# Half-Bridge.net
KiCad netlist of a schematic drawn in Altium Designer
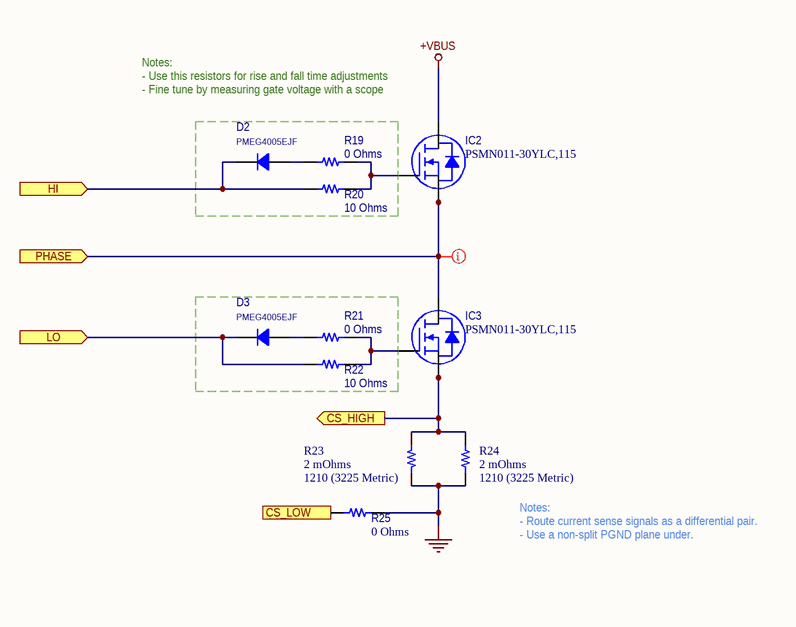
[diagram p0: Half-Bridge.SchDoc]

(export (version "E")
  (design (tool "Eeschema 10.0.6"))
  (components
    (comp (ref "D2")
      (value "PMEG4005EJF")
      (footprint "SOD323F")
      (description "PMEG4005EJ/SOD323/SOD2")
      (fields (field (name "MANUFACTURER") "Nexperia USA Inc."))
      (libsource (lib "Celestial Altium Library - altium_library") (part "Diode"))
    )
    (comp (ref "D3")
      (value "PMEG4005EJF")
      (footprint "SOD323F")
      (description "PMEG4005EJ/SOD323/SOD2")
      (fields (field (name "MANUFACTURER") "Nexperia USA Inc."))
      (libsource (lib "Celestial Altium Library - altium_library") (part "Diode"))
    )
    (comp (ref "IC2")
      (value "PSMN011-30YLC,115")
      (footprint "NXP LFPAK56 SOT669")
      (description "MOSFET N-CH 30V 37A LFPAK")
      (fields (field (name "MANUFACTURER") "Nexperia USA Inc."))
      (libsource (lib "Celestial Altium Library - altium_library") (part "NEXPERIA PSMN LFPAK MOSFET N-CH"))
    )
    (comp (ref "IC3")
      (value "PSMN011-30YLC,115")
      (footprint "NXP LFPAK56 SOT669")
      (description "MOSFET N-CH 30V 37A LFPAK")
      (fields (field (name "MANUFACTURER") "Nexperia USA Inc."))
      (libsource (lib "Celestial Altium Library - altium_library") (part "NEXPERIA PSMN LFPAK MOSFET N-CH"))
    )
    (comp (ref "R19")
      (value "0 Ohms")
      (footprint "RES 0402_1005")
      (description "RESA-AS 0402 0R JUMPER 63MW")
      (fields (field (name "PART NUMBER") "CR0402AJ/-000GAS") (field (name "MANUFACTURER") "Bourns Inc."))
      (libsource (lib "Celestial Altium Library - altium_library") (part "Resistor"))
    )
    (comp (ref "R20")
      (value "10 Ohms")
      (footprint "RES 0402_1005")
      (description "RES SMD 10 OHM 0.5% 1/16W 0402")
      (fields (field (name "PART NUMBER") "RR0510R-100-D") (field (name "MANUFACTURER") "Susumu"))
      (libsource (lib "Celestial Altium Library - altium_library") (part "Resistor"))
    )
    (comp (ref "R21")
      (value "0 Ohms")
      (footprint "RES 0402_1005")
      (description "RESA-AS 0402 0R JUMPER 63MW")
      (fields (field (name "PART NUMBER") "CR0402AJ/-000GAS") (field (name "MANUFACTURER") "Bourns Inc."))
      (libsource (lib "Celestial Altium Library - altium_library") (part "Resistor"))
    )
    (comp (ref "R22")
      (value "10 Ohms")
      (footprint "RES 0402_1005")
      (description "RES SMD 10 OHM 0.5% 1/16W 0402")
      (fields (field (name "PART NUMBER") "RR0510R-100-D") (field (name "MANUFACTURER") "Susumu"))
      (libsource (lib "Celestial Altium Library - altium_library") (part "Resistor"))
    )
    (comp (ref "R23")
      (value "2 mOhms")
      (footprint "RES 1210_3225")
      (description "RES 0.002 OHM 1% 1W 1210")
      (fields
        (field (name "PART NUMBER") "PMR25HZPFV2L00")
        (field (name "DEVICE PACKAGE") "1210 (3225 Metric)")
        (field (name "MANUFACTURER") "Rohm Semiconductor")
      )
      (libsource (lib "Celestial Altium Library - altium_library") (part "Resistor"))
    )
    (comp (ref "R24")
      (value "2 mOhms")
      (footprint "RES 1210_3225")
      (description "RES 0.002 OHM 1% 1W 1210")
      (fields
        (field (name "PART NUMBER") "PMR25HZPFV2L00")
        (field (name "DEVICE PACKAGE") "1210 (3225 Metric)")
        (field (name "MANUFACTURER") "Rohm Semiconductor")
      )
      (libsource (lib "Celestial Altium Library - altium_library") (part "Resistor"))
    )
    (comp (ref "R25")
      (value "0 Ohms")
      (footprint "RES 0603_1608")
      (description "RES SMD 0 OHM JUMPER 1/4W 0603")
      (fields (field (name "PART NUMBER") "CRCW06030000Z0EAHP") (field (name "MANUFACTURER") "Vishay Dale"))
      (libsource (lib "Celestial Altium Library - altium_library") (part "Resistor"))
    )
  )
  (nets
    (net (code "1") (name "+VBUS") (class "Default")
      (node (ref "IC2") (pin "5") (pinfunction "D_5") (pintype "passive"))
    )
    (net (code "2") (name "/CS_HIGH") (class "Default")
      (node (ref "IC3") (pin "1") (pinfunction "S_1") (pintype "passive"))
      (node (ref "IC3") (pin "2") (pinfunction "S_2") (pintype "passive"))
      (node (ref "IC3") (pin "3") (pinfunction "S_3") (pintype "passive"))
      (node (ref "R23") (pin "2") (pinfunction "2_2") (pintype "passive"))
      (node (ref "R24") (pin "2") (pinfunction "2_2") (pintype "passive"))
    )
    (net (code "3") (name "/CS_LOW") (class "Default")
      (node (ref "R25") (pin "1") (pinfunction "1_1") (pintype "passive"))
    )
    (net (code "4") (name "/HI") (class "Default")
      (node (ref "D2") (pin "2") (pinfunction "2_2") (pintype "passive"))
      (node (ref "R20") (pin "1") (pinfunction "1_1") (pintype "passive"))
    )
    (net (code "5") (name "/LO") (class "Default")
      (node (ref "D3") (pin "2") (pinfunction "2_2") (pintype "passive"))
      (node (ref "R22") (pin "1") (pinfunction "1_1") (pintype "passive"))
    )
    (net (code "6") (name "/PHASE") (class "Default")
      (node (ref "IC2") (pin "1") (pinfunction "S_1") (pintype "passive"))
      (node (ref "IC2") (pin "2") (pinfunction "S_2") (pintype "passive"))
      (node (ref "IC2") (pin "3") (pinfunction "S_3") (pintype "passive"))
      (node (ref "IC3") (pin "5") (pinfunction "D_5") (pintype "passive"))
    )
    (net (code "7") (name "GND") (class "Default")
      (node (ref "R23") (pin "1") (pinfunction "1_1") (pintype "passive"))
      (node (ref "R24") (pin "1") (pinfunction "1_1") (pintype "passive"))
      (node (ref "R25") (pin "2") (pinfunction "2_2") (pintype "passive"))
    )
    (net (code "8") (name "Net-(D2-Pad1)") (class "Default")
      (node (ref "D2") (pin "1") (pinfunction "1_1") (pintype "passive"))
      (node (ref "R19") (pin "1") (pinfunction "1_1") (pintype "passive"))
    )
    (net (code "9") (name "Net-(D3-Pad1)") (class "Default")
      (node (ref "D3") (pin "1") (pinfunction "1_1") (pintype "passive"))
      (node (ref "R21") (pin "1") (pinfunction "1_1") (pintype "passive"))
    )
    (net (code "10") (name "Net-(IC2-G)") (class "Default")
      (node (ref "IC2") (pin "4") (pinfunction "G_4") (pintype "passive"))
      (node (ref "R19") (pin "2") (pinfunction "2_2") (pintype "passive"))
      (node (ref "R20") (pin "2") (pinfunction "2_2") (pintype "passive"))
    )
    (net (code "11") (name "Net-(IC3-G)") (class "Default")
      (node (ref "IC3") (pin "4") (pinfunction "G_4") (pintype "passive"))
      (node (ref "R21") (pin "2") (pinfunction "2_2") (pintype "passive"))
      (node (ref "R22") (pin "2") (pinfunction "2_2") (pintype "passive"))
    )
  )
)
